# windmast2.net
KiCad netlist of a schematic drawn in EAGLE
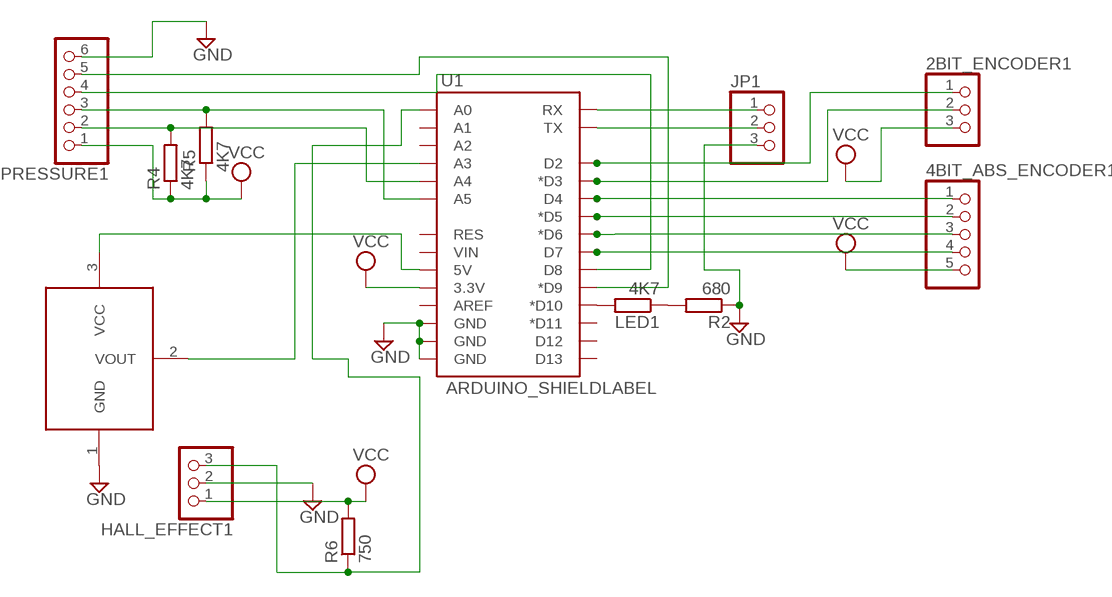
[diagram p0: schematic, sheet 1]

(export (version "E")
  (design (tool "Eeschema 10.0.6"))
  (components
    (comp (ref "2BIT_ENCODER1")
      (value "PINHD-1X3")
      (footprint "eagle-import:1X03")
      (libsource (lib "eagle-import") (part "PINHD-1X3"))
    )
    (comp (ref "4BIT_ABS_ENCODER1")
      (value "PINHD-1X5")
      (footprint "eagle-import:1X05")
      (libsource (lib "eagle-import") (part "PINHD-1X5"))
    )
    (comp (ref "HALL_EFFECT1")
      (value "PINHD-1X3")
      (footprint "eagle-import:1X03")
      (libsource (lib "eagle-import") (part "PINHD-1X3"))
    )
    (comp (ref "IC1")
      (value "LM35")
      (footprint "eagle-import:TO92")
      (libsource (lib "eagle-import") (part "LM35"))
    )
    (comp (ref "JP1")
      (value "PINHD-1X3")
      (footprint "eagle-import:1X03")
      (libsource (lib "eagle-import") (part "PINHD-1X3"))
    )
    (comp (ref "LED1")
      (value "4K7")
      (footprint "eagle-import:R0805")
      (libsource (lib "eagle-import") (part "R-EU_R0805"))
    )
    (comp (ref "PRESSURE1")
      (value "PINHD-1X6")
      (footprint "eagle-import:1X06")
      (libsource (lib "eagle-import") (part "PINHD-1X6"))
    )
    (comp (ref "R2")
      (value "680")
      (footprint "eagle-import:R0805")
      (libsource (lib "eagle-import") (part "R-EU_R0805"))
    )
    (comp (ref "R4")
      (value "4K7")
      (footprint "eagle-import:R0805")
      (libsource (lib "eagle-import") (part "R-EU_R0805"))
    )
    (comp (ref "R5")
      (value "4K7")
      (footprint "eagle-import:R0805")
      (libsource (lib "eagle-import") (part "R-EU_R0805"))
    )
    (comp (ref "R6")
      (value "750")
      (footprint "eagle-import:R0805")
      (libsource (lib "eagle-import") (part "R-EU_R0805"))
    )
    (comp (ref "U1")
      (value "ARDUINO_SHIELDLABEL")
      (footprint "eagle-import:DUEMILANOVE_SHIELD")
      (libsource (lib "eagle-import") (part "ARDUINO_SHIELDLABEL"))
    )
  )
  (nets
    (net (code "1") (name "GND") (class "Default")
      (node (ref "HALL_EFFECT1") (pin "2") (pinfunction "2_2") (pintype "passive"))
      (node (ref "IC1") (pin "1") (pinfunction "GND_1") (pintype "power_in"))
      (node (ref "JP1") (pin "3") (pinfunction "3_3") (pintype "passive"))
      (node (ref "PRESSURE1") (pin "6") (pinfunction "6_6") (pintype "passive"))
      (node (ref "R2") (pin "1") (pinfunction "1_1") (pintype "passive"))
      (node (ref "U1") (pin "GND@0") (pinfunction "GND_GND@0") (pintype "bidirectional"))
      (node (ref "U1") (pin "GND@1") (pinfunction "GND_GND@1") (pintype "bidirectional"))
      (node (ref "U1") (pin "GND@2") (pinfunction "GND_GND@2") (pintype "bidirectional"))
    )
    (net (code "2") (name "Net-(2BIT_ENCODER1-Pad1)") (class "Default")
      (node (ref "2BIT_ENCODER1") (pin "1") (pinfunction "1_1") (pintype "passive"))
      (node (ref "U1") (pin "D2") (pinfunction "D2_D2") (pintype "bidirectional"))
    )
    (net (code "3") (name "Net-(4BIT_ABS_ENCODER1-Pad1)") (class "Default")
      (node (ref "4BIT_ABS_ENCODER1") (pin "1") (pinfunction "1_1") (pintype "passive"))
      (node (ref "U1") (pin "D4") (pinfunction "D4_D4") (pintype "bidirectional"))
    )
    (net (code "4") (name "Net-(4BIT_ABS_ENCODER1-Pad4)") (class "Default")
      (node (ref "4BIT_ABS_ENCODER1") (pin "4") (pinfunction "4_4") (pintype "passive"))
      (node (ref "U1") (pin "D7") (pinfunction "D7_D7") (pintype "bidirectional"))
    )
    (net (code "5") (name "Net-(HALL_EFFECT1-Pad3)") (class "Default")
      (node (ref "HALL_EFFECT1") (pin "3") (pinfunction "3_3") (pintype "passive"))
      (node (ref "R6") (pin "1") (pinfunction "1_1") (pintype "passive"))
      (node (ref "U1") (pin "A0") (pinfunction "A0_A0") (pintype "bidirectional"))
    )
    (net (code "6") (name "Net-(IC1-VCC)") (class "Default")
      (node (ref "IC1") (pin "3") (pinfunction "VCC_3") (pintype "power_in"))
      (node (ref "U1") (pin "5V") (pinfunction "5V_5V") (pintype "bidirectional"))
    )
    (net (code "7") (name "Net-(IC1-VOUT)") (class "Default")
      (node (ref "IC1") (pin "2") (pinfunction "VOUT_2") (pintype "output"))
      (node (ref "U1") (pin "A3") (pinfunction "A3_A3") (pintype "bidirectional"))
    )
    (net (code "8") (name "Net-(JP1-Pad1)") (class "Default")
      (node (ref "JP1") (pin "1") (pinfunction "1_1") (pintype "passive"))
      (node (ref "U1") (pin "RX") (pinfunction "RX_RX") (pintype "bidirectional"))
    )
    (net (code "9") (name "Net-(JP1-Pad2)") (class "Default")
      (node (ref "JP1") (pin "2") (pinfunction "2_2") (pintype "passive"))
      (node (ref "U1") (pin "TX") (pinfunction "TX_TX") (pintype "bidirectional"))
    )
    (net (code "10") (name "Net-(LED1-Pad1)") (class "Default")
      (node (ref "LED1") (pin "1") (pinfunction "1_1") (pintype "passive"))
      (node (ref "R2") (pin "2") (pinfunction "2_2") (pintype "passive"))
    )
    (net (code "11") (name "Net-(PRESSURE1-Pad2)") (class "Default")
      (node (ref "PRESSURE1") (pin "2") (pinfunction "2_2") (pintype "passive"))
      (node (ref "R4") (pin "2") (pinfunction "2_2") (pintype "passive"))
      (node (ref "U1") (pin "A4") (pinfunction "A4_A4") (pintype "bidirectional"))
    )
    (net (code "12") (name "Net-(PRESSURE1-Pad3)") (class "Default")
      (node (ref "PRESSURE1") (pin "3") (pinfunction "3_3") (pintype "passive"))
      (node (ref "R5") (pin "2") (pinfunction "2_2") (pintype "passive"))
      (node (ref "U1") (pin "A5") (pinfunction "A5_A5") (pintype "bidirectional"))
    )
    (net (code "13") (name "Net-(PRESSURE1-Pad4)") (class "Default")
      (node (ref "PRESSURE1") (pin "4") (pinfunction "4_4") (pintype "passive"))
      (node (ref "U1") (pin "D8") (pinfunction "D8_D8") (pintype "bidirectional"))
    )
    (net (code "14") (name "Net-(U1-*D3)") (class "Default")
      (node (ref "2BIT_ENCODER1") (pin "2") (pinfunction "2_2") (pintype "passive"))
      (node (ref "U1") (pin "D3") (pinfunction "*D3_D3") (pintype "bidirectional"))
    )
    (net (code "15") (name "Net-(U1-*D5)") (class "Default")
      (node (ref "4BIT_ABS_ENCODER1") (pin "2") (pinfunction "2_2") (pintype "passive"))
      (node (ref "U1") (pin "D5") (pinfunction "*D5_D5") (pintype "bidirectional"))
    )
    (net (code "16") (name "Net-(U1-*D6)") (class "Default")
      (node (ref "4BIT_ABS_ENCODER1") (pin "3") (pinfunction "3_3") (pintype "passive"))
      (node (ref "U1") (pin "D6") (pinfunction "*D6_D6") (pintype "bidirectional"))
    )
    (net (code "17") (name "Net-(U1-*D9)") (class "Default")
      (node (ref "PRESSURE1") (pin "5") (pinfunction "5_5") (pintype "passive"))
      (node (ref "U1") (pin "D9") (pinfunction "*D9_D9") (pintype "bidirectional"))
    )
    (net (code "18") (name "Net-(U1-*D10)") (class "Default")
      (node (ref "LED1") (pin "2") (pinfunction "2_2") (pintype "passive"))
      (node (ref "U1") (pin "D10") (pinfunction "*D10_D10") (pintype "bidirectional"))
    )
    (net (code "19") (name "VCC") (class "Default")
      (node (ref "2BIT_ENCODER1") (pin "3") (pinfunction "3_3") (pintype "passive"))
      (node (ref "4BIT_ABS_ENCODER1") (pin "5") (pinfunction "5_5") (pintype "passive"))
      (node (ref "HALL_EFFECT1") (pin "1") (pinfunction "1_1") (pintype "passive"))
      (node (ref "PRESSURE1") (pin "1") (pinfunction "1_1") (pintype "passive"))
      (node (ref "R4") (pin "1") (pinfunction "1_1") (pintype "passive"))
      (node (ref "R5") (pin "1") (pinfunction "1_1") (pintype "passive"))
      (node (ref "R6") (pin "2") (pinfunction "2_2") (pintype "passive"))
      (node (ref "U1") (pin "3.3V") (pinfunction "3.3V_3.3V") (pintype "bidirectional"))
    )
    (net (code "20") (name "unconnected-(U1-*D11-PadD11)") (class "Default")
      (node (ref "U1") (pin "D11") (pinfunction "*D11_D11") (pintype "bidirectional"))
    )
    (net (code "21") (name "unconnected-(U1-PadA1)") (class "Default")
      (node (ref "U1") (pin "A1") (pinfunction "A1_A1") (pintype "bidirectional"))
    )
    (net (code "22") (name "unconnected-(U1-PadA2)") (class "Default")
      (node (ref "U1") (pin "A2") (pinfunction "A2_A2") (pintype "bidirectional"))
    )
    (net (code "23") (name "unconnected-(U1-PadAREF)") (class "Default")
      (node (ref "U1") (pin "AREF") (pinfunction "AREF_AREF") (pintype "bidirectional"))
    )
    (net (code "24") (name "unconnected-(U1-PadD12)") (class "Default")
      (node (ref "U1") (pin "D12") (pinfunction "D12_D12") (pintype "bidirectional"))
    )
    (net (code "25") (name "unconnected-(U1-PadD13)") (class "Default")
      (node (ref "U1") (pin "D13") (pinfunction "D13_D13") (pintype "bidirectional"))
    )
    (net (code "26") (name "unconnected-(U1-PadRES)") (class "Default")
      (node (ref "U1") (pin "RES") (pinfunction "RES_RES") (pintype "bidirectional"))
    )
    (net (code "27") (name "unconnected-(U1-PadVIN)") (class "Default")
      (node (ref "U1") (pin "VIN") (pinfunction "VIN_VIN") (pintype "bidirectional"))
    )
  )
)
